# MCU.net
KiCad netlist of a schematic drawn in Altium Designer
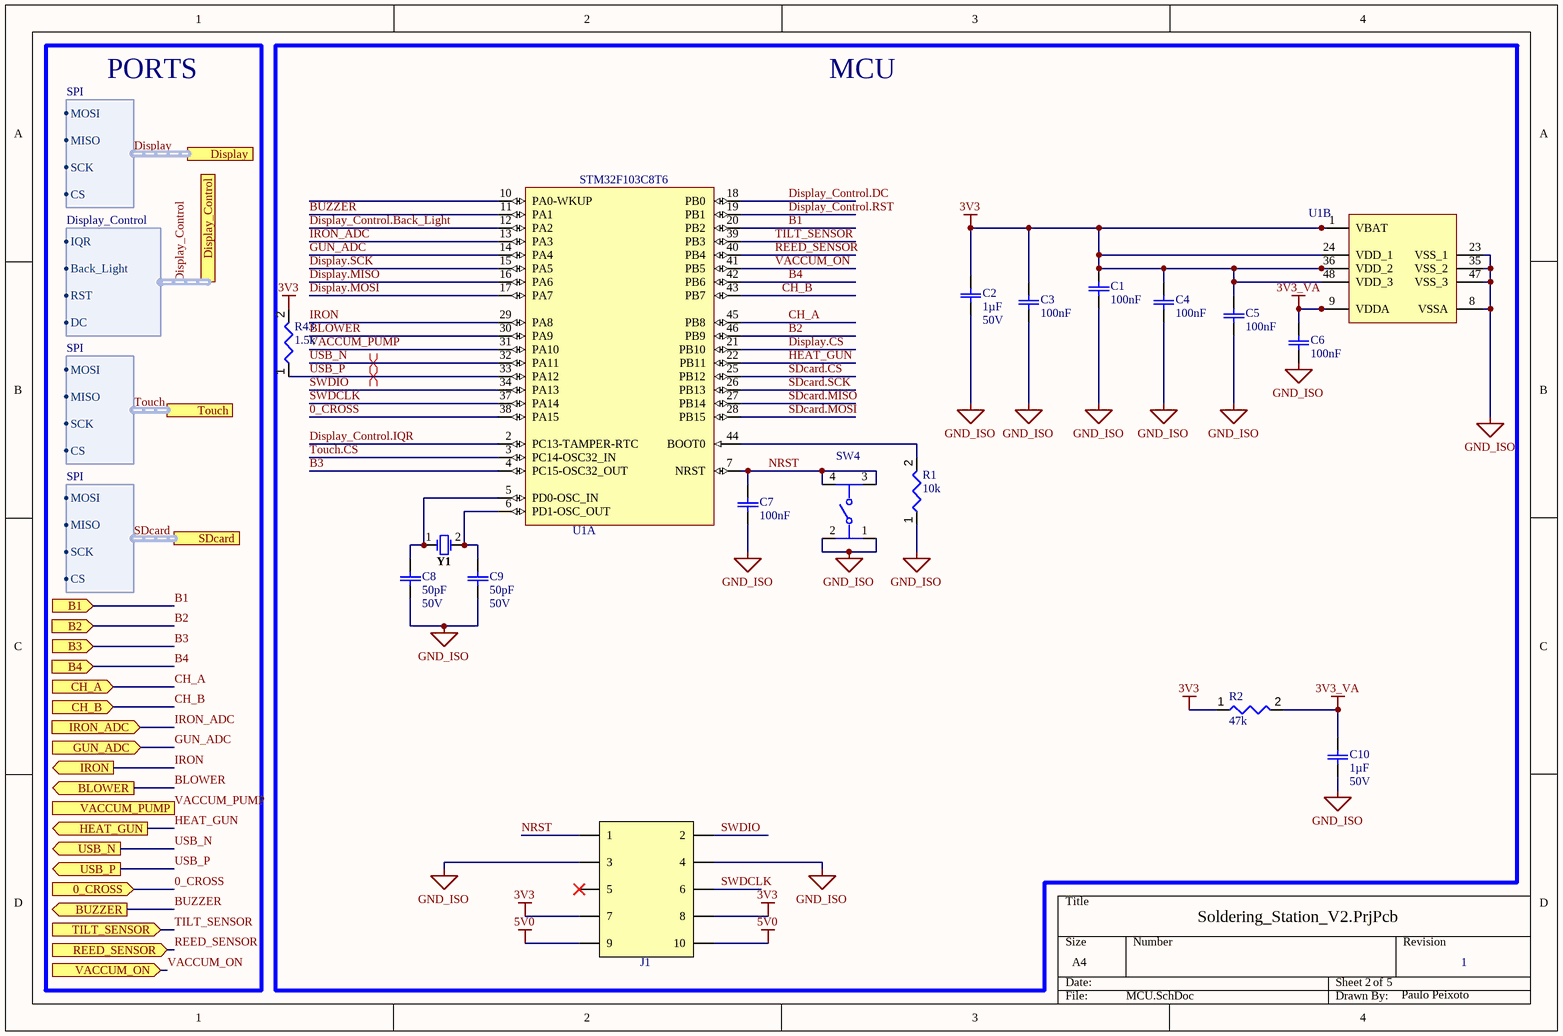
[diagram p0: MCU.SchDoc]

(export (version "E")
  (design (tool "Eeschema 10.0.6"))
  (components
    (comp (ref "C1")
      (value "100nF")
      (footprint "Generic Ceramic 0402 CAP")
      (description "Ceramic Capacitor, Ceramic, 50V, 10% +Tol, 10% -Tol, X7R, 15% TC, 0.1uF, Surface Mount, 0402")
      (fields (field (name "Comment") "CAP-MLCC_SMD-0402_MR-GCM_n_100nF_50V_10%_X7R"))
      (libsource (lib "Paulo Peixoto") (part "CAP_Ceramic"))
    )
    (comp (ref "C2")
      (value "1µF")
      (footprint "Generic Ceramic 0603 CAP")
      (description "Multilayer Ceramic Capacitors MLCC - SMD/SMT 0603 50Vdc 1.0uF X5R 10%")
      (fields
        (field (name "VOLTAGE RATING") "50V")
        (field (name "TOLERANCE") "10%")
        (field (name "Comment") "CAP-MLCC_SMD-0603_MR-GRT_u_1uF_50V_10%_X5R")
      )
      (libsource (lib "Paulo Peixoto") (part "CAP_Ceramic"))
    )
    (comp (ref "C3")
      (value "100nF")
      (footprint "Generic Ceramic 0402 CAP")
      (description "Ceramic Capacitor, Ceramic, 50V, 10% +Tol, 10% -Tol, X7R, 15% TC, 0.1uF, Surface Mount, 0402")
      (fields (field (name "Comment") "CAP-MLCC_SMD-0402_MR-GCM_n_100nF_50V_10%_X7R"))
      (libsource (lib "Paulo Peixoto") (part "CAP_Ceramic"))
    )
    (comp (ref "C4")
      (value "100nF")
      (footprint "Generic Ceramic 0402 CAP")
      (description "Ceramic Capacitor, Ceramic, 50V, 10% +Tol, 10% -Tol, X7R, 15% TC, 0.1uF, Surface Mount, 0402")
      (fields (field (name "Comment") "CAP-MLCC_SMD-0402_MR-GCM_n_100nF_50V_10%_X7R"))
      (libsource (lib "Paulo Peixoto") (part "CAP_Ceramic"))
    )
    (comp (ref "C5")
      (value "100nF")
      (footprint "Generic Ceramic 0402 CAP")
      (description "Ceramic Capacitor, Ceramic, 50V, 10% +Tol, 10% -Tol, X7R, 15% TC, 0.1uF, Surface Mount, 0402")
      (fields (field (name "Comment") "CAP-MLCC_SMD-0402_MR-GCM_n_100nF_50V_10%_X7R"))
      (libsource (lib "Paulo Peixoto") (part "CAP_Ceramic"))
    )
    (comp (ref "C6")
      (value "100nF")
      (footprint "Generic Ceramic 0402 CAP")
      (description "Ceramic Capacitor, Ceramic, 50V, 10% +Tol, 10% -Tol, X7R, 15% TC, 0.1uF, Surface Mount, 0402")
      (fields (field (name "Comment") "CAP-MLCC_SMD-0402_MR-GCM_n_100nF_50V_10%_X7R"))
      (libsource (lib "Paulo Peixoto") (part "CAP_Ceramic"))
    )
    (comp (ref "C7")
      (value "100nF")
      (footprint "Generic Ceramic 0402 CAP")
      (description "Ceramic Capacitor, Ceramic, 50V, 10% +Tol, 10% -Tol, X7R, 15% TC, 0.1uF, Surface Mount, 0402")
      (fields (field (name "Comment") "CAP-MLCC_SMD-0402_MR-GCM_n_100nF_50V_10%_X7R"))
      (libsource (lib "Paulo Peixoto") (part "CAP_Ceramic"))
    )
    (comp (ref "C8")
      (value "50pF")
      (footprint "Generic Ceramic 0603 CAP")
      (description "Surface Mount Ceramic Multilayer Capacitor 50pF 5% C0G 50V 0603 Paper T/R")
      (fields
        (field (name "VOLTAGE RATING") "50V")
        (field (name "Comment") "CAP-MLCC_SMD-0603_YGE-CC_p_50pF_50V_5%_C0G")
      )
      (libsource (lib "Paulo Peixoto") (part "CAP_Ceramic"))
    )
    (comp (ref "C9")
      (value "50pF")
      (footprint "Generic Ceramic 0603 CAP")
      (description "Surface Mount Ceramic Multilayer Capacitor 50pF 5% C0G 50V 0603 Paper T/R")
      (fields
        (field (name "VOLTAGE RATING") "50V")
        (field (name "Comment") "CAP-MLCC_SMD-0603_YGE-CC_p_50pF_50V_5%_C0G")
      )
      (libsource (lib "Paulo Peixoto") (part "CAP_Ceramic"))
    )
    (comp (ref "C10")
      (value "1µF")
      (footprint "Generic Ceramic 0603 CAP")
      (description "Multilayer Ceramic Capacitors MLCC - SMD/SMT 0603 50Vdc 1.0uF X5R 10%")
      (fields
        (field (name "VOLTAGE RATING") "50V")
        (field (name "TOLERANCE") "10%")
        (field (name "Comment") "CAP-MLCC_SMD-0603_MR-GRT_u_1uF_50V_10%_X5R")
      )
      (libsource (lib "Paulo Peixoto") (part "CAP_Ceramic"))
    )
    (comp (ref "J1")
      (value "302-S101")
      (footprint "FP-302-S101-MFG")
      (description "Conn Shrouded Header (4 Sides) HDR 10 POS 2.54mm Solder ST Thru-Hole")
      (libsource (lib "Paulo Peixoto") (part "302-S101-Symbol-1"))
    )
    (comp (ref "R1")
      (value "10k")
      (footprint "Generic_0603_RES")
      (fields
        (field (name "TOLERANCE") "1%")
        (field (name "POWER") "100mW")
        (field (name "Comment") "RES-TK_SMD-0603_VIS-CRCW_K_10K_1/10W_1%")
      )
      (libsource (lib "Paulo Peixoto") (part "Res"))
    )
    (comp (ref "R2")
      (value "47k")
      (footprint "Generic_0603_RES")
      (fields
        (field (name "TOLERANCE") "1%")
        (field (name "POWER") "100mW")
        (field (name "Comment") "RES-TK_SMD-0603_VIS-CRCW_K_47K_1/10W_1%")
      )
      (libsource (lib "Paulo Peixoto") (part "Res"))
    )
    (comp (ref "R43")
      (value "1.5k")
      (footprint "Generic_0402__RES")
      (description "Surface Mount Thick Film Resistor, AEC-Q200 CRCW Series, 1.5 kohm, 125 mW, - 1%, 50 V")
      (fields
        (field (name "TOLERANCE") "1%")
        (field (name "Comment") "RES-TK_SMD-0402_VIS-CRCW_K_1.5K_1/10W_1%")
      )
      (libsource (lib "Paulo Peixoto") (part "Res"))
    )
    (comp (ref "SW4")
      (value "TL1105AF160Q")
      (footprint "FP-TL1105AF160Q-MFG")
      (description "SWITCH TACTILE SPST-NO 0.05A 12V")
      (libsource (lib "Soldering_Station_V2") (part "CMP-17879-000016-1"))
    )
    (comp (ref "U1")
      (value "STM32F103C8T6")
      (footprint "STM-LQFP48_L")
      (libsource (lib "Altium Content Vault") (part "MC-ARM-STM32F103X8_B-SQ48"))
    )
    (comp (ref "Y1")
      (value "FOXSLF/080-20")
      (footprint "FOX-FOXSLF080-20")
      (description "Resistance Weld Thru-Hole Crystal, 8 MHz, -20 to 70 degC, 2-Pin THD, RoHS, Bulk")
      (libsource (lib "Altium Content Vault") (part "XTAL-1-2-2"))
    )
  )
  (nets
    (net (code "5") (name "/0_CROSS") (class "Default")
      (node (ref "U1") (pin "38") (pinfunction "PA15_38") (pintype "bidirectional"))
    )
    (net (code "6") (name "/B1") (class "Default")
      (node (ref "U1") (pin "20") (pinfunction "PB2_20") (pintype "bidirectional"))
    )
    (net (code "7") (name "/B2") (class "Default")
      (node (ref "U1") (pin "46") (pinfunction "PB9_46") (pintype "bidirectional"))
    )
    (net (code "8") (name "/B3") (class "Default")
      (node (ref "U1") (pin "4") (pinfunction "PC15-OSC32_OUT_4") (pintype "bidirectional"))
    )
    (net (code "9") (name "/B4") (class "Default")
      (node (ref "U1") (pin "42") (pinfunction "PB6_42") (pintype "bidirectional"))
    )
    (net (code "10") (name "/BLOWER") (class "Default")
      (node (ref "U1") (pin "30") (pinfunction "PA9_30") (pintype "bidirectional"))
    )
    (net (code "11") (name "/BUZZER") (class "Default")
      (node (ref "U1") (pin "11") (pinfunction "PA1_11") (pintype "bidirectional"))
    )
    (net (code "12") (name "/CH_A") (class "Default")
      (node (ref "U1") (pin "45") (pinfunction "PB8_45") (pintype "bidirectional"))
    )
    (net (code "13") (name "/CH_B") (class "Default")
      (node (ref "U1") (pin "43") (pinfunction "PB7_43") (pintype "bidirectional"))
    )
    (net (code "14") (name "/Display.CS") (class "Default")
      (node (ref "U1") (pin "21") (pinfunction "PB10_21") (pintype "bidirectional"))
    )
    (net (code "15") (name "/Display.MISO") (class "Default")
      (node (ref "U1") (pin "16") (pinfunction "PA6_16") (pintype "bidirectional"))
    )
    (net (code "16") (name "/Display.MOSI") (class "Default")
      (node (ref "U1") (pin "17") (pinfunction "PA7_17") (pintype "bidirectional"))
    )
    (net (code "17") (name "/Display.SCK") (class "Default")
      (node (ref "U1") (pin "15") (pinfunction "PA5_15") (pintype "bidirectional"))
    )
    (net (code "18") (name "/Display_Control.Back_Light") (class "Default")
      (node (ref "U1") (pin "12") (pinfunction "PA2_12") (pintype "bidirectional"))
    )
    (net (code "19") (name "/Display_Control.DC") (class "Default")
      (node (ref "U1") (pin "18") (pinfunction "PB0_18") (pintype "bidirectional"))
    )
    (net (code "20") (name "/Display_Control.IQR") (class "Default")
      (node (ref "U1") (pin "2") (pinfunction "PC13-TAMPER-RTC_2") (pintype "bidirectional"))
    )
    (net (code "21") (name "/Display_Control.RST") (class "Default")
      (node (ref "U1") (pin "19") (pinfunction "PB1_19") (pintype "bidirectional"))
    )
    (net (code "24") (name "/GUN_ADC") (class "Default")
      (node (ref "U1") (pin "14") (pinfunction "PA4_14") (pintype "bidirectional"))
    )
    (net (code "25") (name "/HEAT_GUN") (class "Default")
      (node (ref "U1") (pin "22") (pinfunction "PB11_22") (pintype "bidirectional"))
    )
    (net (code "26") (name "/IRON") (class "Default")
      (node (ref "U1") (pin "29") (pinfunction "PA8_29") (pintype "bidirectional"))
    )
    (net (code "27") (name "/IRON_ADC") (class "Default")
      (node (ref "U1") (pin "13") (pinfunction "PA3_13") (pintype "bidirectional"))
    )
    (net (code "28") (name "/NRST") (class "Default")
      (node (ref "C7") (pin "2") (pinfunction "2_2") (pintype "passive"))
      (node (ref "J1") (pin "1") (pinfunction "1_1") (pintype "passive"))
      (node (ref "SW4") (pin "3") (pinfunction "3_3") (pintype "passive"))
      (node (ref "SW4") (pin "4") (pinfunction "4_4") (pintype "passive"))
      (node (ref "U1") (pin "7") (pinfunction "NRST_7") (pintype "bidirectional"))
    )
    (net (code "29") (name "/REED_SENSOR") (class "Default")
      (node (ref "U1") (pin "40") (pinfunction "PB4_40") (pintype "bidirectional"))
    )
    (net (code "30") (name "/SDcard.CS") (class "Default")
      (node (ref "U1") (pin "25") (pinfunction "PB12_25") (pintype "bidirectional"))
    )
    (net (code "31") (name "/SDcard.MISO") (class "Default")
      (node (ref "U1") (pin "27") (pinfunction "PB14_27") (pintype "bidirectional"))
    )
    (net (code "32") (name "/SDcard.MOSI") (class "Default")
      (node (ref "U1") (pin "28") (pinfunction "PB15_28") (pintype "bidirectional"))
    )
    (net (code "33") (name "/SDcard.SCK") (class "Default")
      (node (ref "U1") (pin "26") (pinfunction "PB13_26") (pintype "bidirectional"))
    )
    (net (code "35") (name "/SWDCLK") (class "Default")
      (node (ref "J1") (pin "6") (pinfunction "6_6") (pintype "passive"))
      (node (ref "U1") (pin "37") (pinfunction "PA14_37") (pintype "bidirectional"))
    )
    (net (code "36") (name "/SWDIO") (class "Default")
      (node (ref "J1") (pin "2") (pinfunction "2_2") (pintype "passive"))
      (node (ref "U1") (pin "34") (pinfunction "PA13_34") (pintype "bidirectional"))
    )
    (net (code "37") (name "/TILT_SENSOR") (class "Default")
      (node (ref "U1") (pin "39") (pinfunction "PB3_39") (pintype "bidirectional"))
    )
    (net (code "38") (name "/Touch.CS") (class "Default")
      (node (ref "U1") (pin "3") (pinfunction "PC14-OSC32_IN_3") (pintype "bidirectional"))
    )
    (net (code "40") (name "/USB_N") (class "Default")
      (node (ref "U1") (pin "32") (pinfunction "PA11_32") (pintype "bidirectional"))
    )
    (net (code "41") (name "/USB_P") (class "Default")
      (node (ref "R43") (pin "1") (pinfunction "1_1") (pintype "passive"))
      (node (ref "U1") (pin "33") (pinfunction "PA12_33") (pintype "bidirectional"))
    )
    (net (code "42") (name "/VACCUM_ON") (class "Default")
      (node (ref "U1") (pin "41") (pinfunction "PB5_41") (pintype "bidirectional"))
    )
    (net (code "43") (name "/VACCUM_PUMP") (class "Default")
      (node (ref "U1") (pin "31") (pinfunction "PA10_31") (pintype "bidirectional"))
    )
    (net (code "44") (name "3V3") (class "Default")
      (node (ref "C1") (pin "2") (pinfunction "2_2") (pintype "passive"))
      (node (ref "C2") (pin "2") (pinfunction "2_2") (pintype "passive"))
      (node (ref "C3") (pin "2") (pinfunction "2_2") (pintype "passive"))
      (node (ref "C4") (pin "2") (pinfunction "2_2") (pintype "passive"))
      (node (ref "C5") (pin "2") (pinfunction "2_2") (pintype "passive"))
      (node (ref "J1") (pin "7") (pinfunction "7_7") (pintype "passive"))
      (node (ref "J1") (pin "8") (pinfunction "8_8") (pintype "passive"))
      (node (ref "R2") (pin "1") (pinfunction "1_1") (pintype "passive"))
      (node (ref "R43") (pin "2") (pinfunction "2_2") (pintype "passive"))
      (node (ref "U1") (pin "1") (pinfunction "VBAT_1") (pintype "power_in"))
      (node (ref "U1") (pin "24") (pinfunction "VDD_1_24") (pintype "power_in"))
      (node (ref "U1") (pin "36") (pinfunction "VDD_2_36") (pintype "power_in"))
      (node (ref "U1") (pin "48") (pinfunction "VDD_3_48") (pintype "power_in"))
    )
    (net (code "45") (name "3V3_VA") (class "Default")
      (node (ref "C10") (pin "2") (pinfunction "2_2") (pintype "passive"))
      (node (ref "C6") (pin "2") (pinfunction "2_2") (pintype "passive"))
      (node (ref "R2") (pin "2") (pinfunction "2_2") (pintype "passive"))
      (node (ref "U1") (pin "9") (pinfunction "VDDA_9") (pintype "power_in"))
    )
    (net (code "46") (name "5V0") (class "Default")
      (node (ref "J1") (pin "10") (pinfunction "10_10") (pintype "passive"))
      (node (ref "J1") (pin "9") (pinfunction "9_9") (pintype "passive"))
    )
    (net (code "47") (name "GND_ISO") (class "Default")
      (node (ref "C1") (pin "1") (pinfunction "1_1") (pintype "passive"))
      (node (ref "C10") (pin "1") (pinfunction "1_1") (pintype "passive"))
      (node (ref "C2") (pin "1") (pinfunction "1_1") (pintype "passive"))
      (node (ref "C3") (pin "1") (pinfunction "1_1") (pintype "passive"))
      (node (ref "C4") (pin "1") (pinfunction "1_1") (pintype "passive"))
      (node (ref "C5") (pin "1") (pinfunction "1_1") (pintype "passive"))
      (node (ref "C6") (pin "1") (pinfunction "1_1") (pintype "passive"))
      (node (ref "C7") (pin "1") (pinfunction "1_1") (pintype "passive"))
      (node (ref "C8") (pin "2") (pinfunction "2_2") (pintype "passive"))
      (node (ref "C9") (pin "2") (pinfunction "2_2") (pintype "passive"))
      (node (ref "J1") (pin "3") (pinfunction "3_3") (pintype "passive"))
      (node (ref "J1") (pin "4") (pinfunction "4_4") (pintype "passive"))
      (node (ref "R1") (pin "1") (pinfunction "1_1") (pintype "passive"))
      (node (ref "SW4") (pin "1") (pinfunction "1_1") (pintype "passive"))
      (node (ref "SW4") (pin "2") (pinfunction "2_2") (pintype "passive"))
      (node (ref "U1") (pin "23") (pinfunction "VSS_1_23") (pintype "power_in"))
      (node (ref "U1") (pin "35") (pinfunction "VSS_2_35") (pintype "power_in"))
      (node (ref "U1") (pin "47") (pinfunction "VSS_3_47") (pintype "power_in"))
      (node (ref "U1") (pin "8") (pinfunction "VSSA_8") (pintype "power_in"))
    )
    (net (code "48") (name "Net-(U1A-BOOT0)") (class "Default")
      (node (ref "R1") (pin "2") (pinfunction "2_2") (pintype "passive"))
      (node (ref "U1") (pin "44") (pinfunction "BOOT0_44") (pintype "input"))
    )
    (net (code "49") (name "Net-(U1A-PD0-OSC_IN)") (class "Default")
      (node (ref "C8") (pin "1") (pinfunction "1_1") (pintype "passive"))
      (node (ref "U1") (pin "5") (pinfunction "PD0-OSC_IN_5") (pintype "bidirectional"))
      (node (ref "Y1") (pin "1") (pinfunction "1_1") (pintype "passive"))
    )
    (net (code "50") (name "Net-(U1A-PD1-OSC_OUT)") (class "Default")
      (node (ref "C9") (pin "1") (pinfunction "1_1") (pintype "passive"))
      (node (ref "U1") (pin "6") (pinfunction "PD1-OSC_OUT_6") (pintype "bidirectional"))
      (node (ref "Y1") (pin "2") (pinfunction "2_2") (pintype "passive"))
    )
    (net (code "51") (name "unconnected-(J1-Pad5)") (class "Default")
      (node (ref "J1") (pin "5") (pinfunction "5_5") (pintype "passive+no_connect"))
    )
    (net (code "52") (name "unconnected-(U1A-PA0-WKUP-Pad10)") (class "Default")
      (node (ref "U1") (pin "10") (pinfunction "PA0-WKUP_10") (pintype "bidirectional"))
    )
  )
)
